# bjt-general.net
KiCad netlist of a schematic drawn in EAGLE
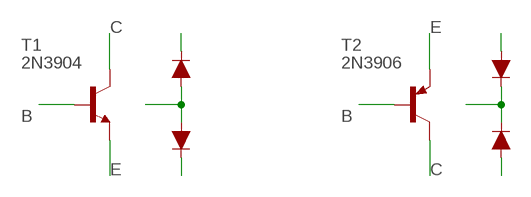
[diagram p0: schematic, sheet 1]

(export (version "E")
  (design (tool "Eeschema 10.0.6"))
  (components
    (comp (ref "D1")
      (value "200mA/100V/1V")
      (footprint "eagle-import:DIODE-1N4148")
      (libsource (lib "eagle-import") (part "DIODE-1N4148"))
    )
    (comp (ref "D2")
      (value "200mA/100V/1V")
      (footprint "eagle-import:DIODE-1N4148")
      (libsource (lib "eagle-import") (part "DIODE-1N4148"))
    )
    (comp (ref "D3")
      (value "200mA/100V/1V")
      (footprint "eagle-import:DIODE-1N4148")
      (libsource (lib "eagle-import") (part "DIODE-1N4148"))
    )
    (comp (ref "D4")
      (value "200mA/100V/1V")
      (footprint "eagle-import:DIODE-1N4148")
      (libsource (lib "eagle-import") (part "DIODE-1N4148"))
    )
    (comp (ref "T1")
      (value "2N3904")
      (footprint "eagle-import:TO92")
      (libsource (lib "eagle-import") (part "2N3904"))
    )
    (comp (ref "T2")
      (value "2N3906")
      (footprint "eagle-import:TO92")
      (libsource (lib "eagle-import") (part "2N3906"))
    )
  )
  (nets
    (net (code "1") (name "/B") (class "Default")
      (node (ref "T1") (pin "2") (pinfunction "B_2") (pintype "passive"))
      (node (ref "T2") (pin "2") (pinfunction "B_2") (pintype "passive"))
    )
    (net (code "2") (name "/C") (class "Default")
      (node (ref "T1") (pin "1") (pinfunction "C_1") (pintype "passive"))
      (node (ref "T2") (pin "1") (pinfunction "C_1") (pintype "passive"))
    )
    (net (code "3") (name "/E") (class "Default")
      (node (ref "T1") (pin "3") (pinfunction "E_3") (pintype "passive"))
      (node (ref "T2") (pin "3") (pinfunction "E_3") (pintype "passive"))
    )
    (net (code "4") (name "Net-(D1-PadA)") (class "Default")
      (node (ref "D1") (pin "A") (pinfunction "A_A") (pintype "passive"))
      (node (ref "D2") (pin "A") (pinfunction "A_A") (pintype "passive"))
    )
    (net (code "5") (name "Net-(D3-PadC)") (class "Default")
      (node (ref "D3") (pin "C") (pinfunction "C_C") (pintype "passive"))
      (node (ref "D4") (pin "C") (pinfunction "C_C") (pintype "passive"))
    )
    (net (code "6") (name "unconnected-(D1-PadC)") (class "Default")
      (node (ref "D1") (pin "C") (pinfunction "C_C") (pintype "passive"))
    )
    (net (code "7") (name "unconnected-(D2-PadC)") (class "Default")
      (node (ref "D2") (pin "C") (pinfunction "C_C") (pintype "passive"))
    )
    (net (code "8") (name "unconnected-(D3-PadA)") (class "Default")
      (node (ref "D3") (pin "A") (pinfunction "A_A") (pintype "passive"))
    )
    (net (code "9") (name "unconnected-(D4-PadA)") (class "Default")
      (node (ref "D4") (pin "A") (pinfunction "A_A") (pintype "passive"))
    )
  )
)
